# SCH_05_Analog_Mux.net
KiCad netlist of a schematic drawn in Altium Designer
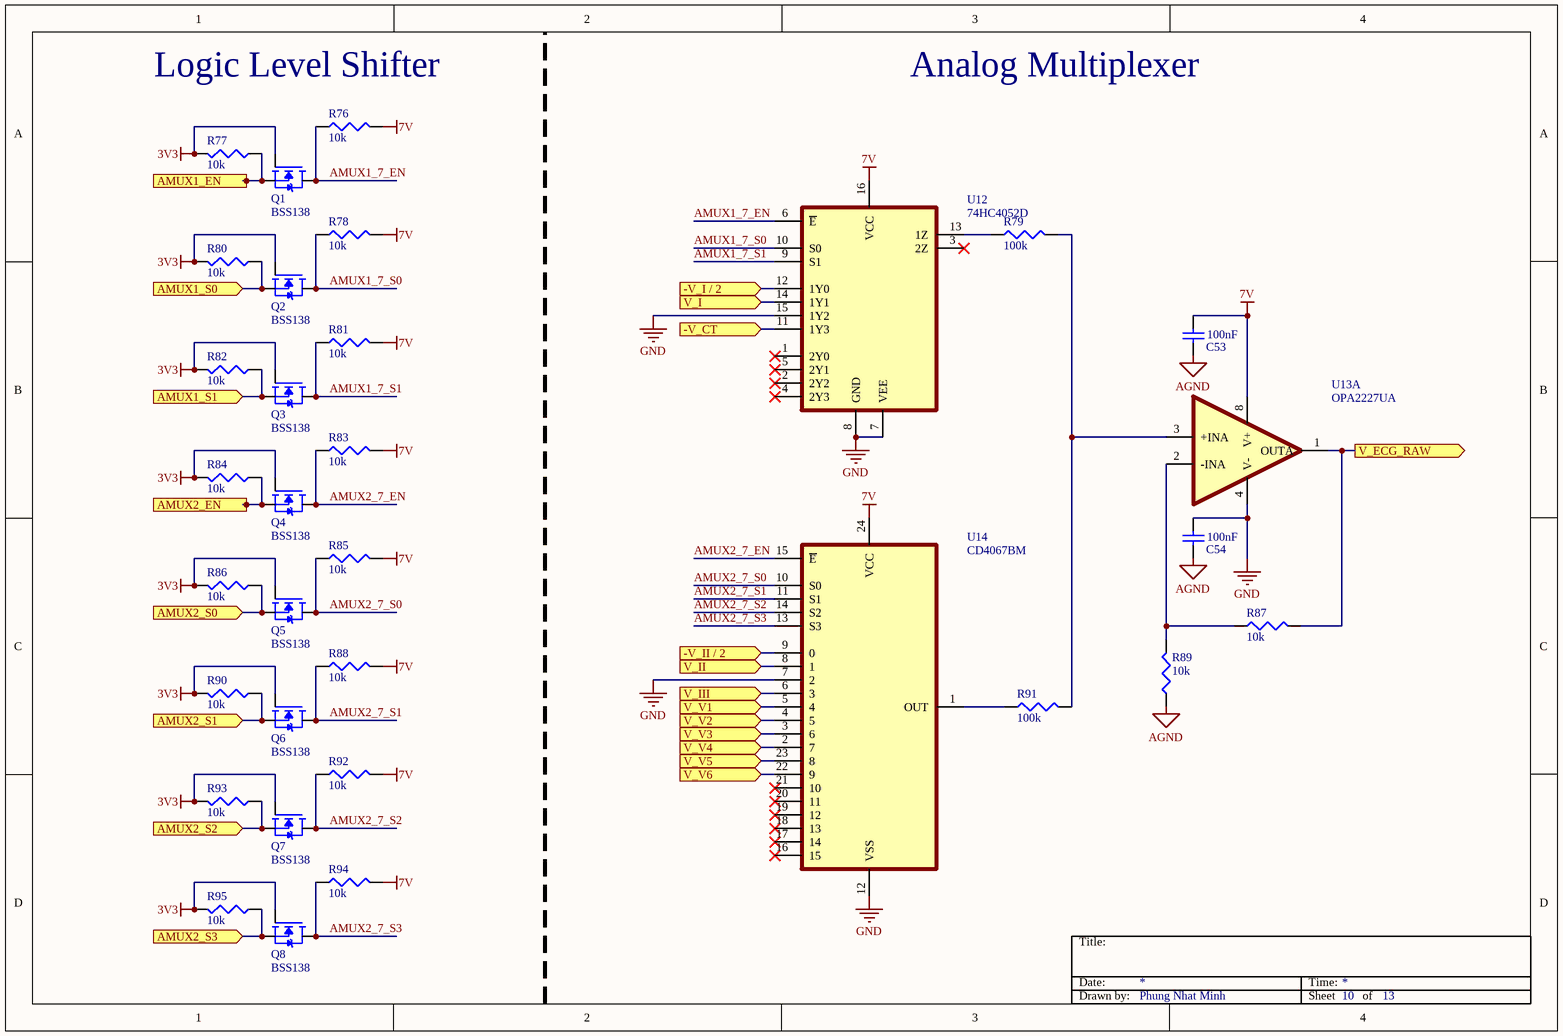
[diagram p0: SCH_05_Analog_Mux.SchDoc]

(export (version "E")
  (design (tool "Eeschema 10.0.6"))
  (components
    (comp (ref "C53")
      (value "100nF")
      (footprint "WCAP-CSGP_0603_L1.6W0.8H0.8_Reflow")
      (description "WCAP-CSGP Multilayer Ceramic Chip Capacitor, General Purpose, size 0603, X7R, 100nF, 50VDC")
      (fields
        (field (name "MANUFACTURER PART NUMBER") "885012206095")
        (field (name "MANUFACTURER") "Wurth Elektronik")
      )
      (libsource (lib "Altium_WCAP-CSGP (rev24b)") (part "885012206095"))
    )
    (comp (ref "C54")
      (value "100nF")
      (footprint "WCAP-CSGP_0603_L1.6W0.8H0.8_Reflow")
      (description "WCAP-CSGP Multilayer Ceramic Chip Capacitor, General Purpose, size 0603, X7R, 100nF, 50VDC")
      (fields
        (field (name "MANUFACTURER PART NUMBER") "885012206095")
        (field (name "MANUFACTURER") "Wurth Elektronik")
      )
      (libsource (lib "Altium_WCAP-CSGP (rev24b)") (part "885012206095"))
    )
    (comp (ref "Q1")
      (value "BSS138")
      (footprint "SOT95P240X111-3N")
      (description "N-Channel 50V 220mA (Ta) 360mW (Ta) Surface Mount SOT-23-3")
      (fields (field (name "MF") "ON Semiconductor"))
      (libsource (lib "BSS138") (part "BSS138"))
    )
    (comp (ref "Q2")
      (value "BSS138")
      (footprint "SOT95P240X111-3N")
      (description "N-Channel 50V 220mA (Ta) 360mW (Ta) Surface Mount SOT-23-3")
      (fields (field (name "MF") "ON Semiconductor"))
      (libsource (lib "BSS138") (part "BSS138"))
    )
    (comp (ref "Q3")
      (value "BSS138")
      (footprint "SOT95P240X111-3N")
      (description "N-Channel 50V 220mA (Ta) 360mW (Ta) Surface Mount SOT-23-3")
      (fields (field (name "MF") "ON Semiconductor"))
      (libsource (lib "BSS138") (part "BSS138"))
    )
    (comp (ref "Q4")
      (value "BSS138")
      (footprint "SOT95P240X111-3N")
      (description "N-Channel 50V 220mA (Ta) 360mW (Ta) Surface Mount SOT-23-3")
      (fields (field (name "MF") "ON Semiconductor"))
      (libsource (lib "BSS138") (part "BSS138"))
    )
    (comp (ref "Q5")
      (value "BSS138")
      (footprint "SOT95P240X111-3N")
      (description "N-Channel 50V 220mA (Ta) 360mW (Ta) Surface Mount SOT-23-3")
      (fields (field (name "MF") "ON Semiconductor"))
      (libsource (lib "BSS138") (part "BSS138"))
    )
    (comp (ref "Q6")
      (value "BSS138")
      (footprint "SOT95P240X111-3N")
      (description "N-Channel 50V 220mA (Ta) 360mW (Ta) Surface Mount SOT-23-3")
      (fields (field (name "MF") "ON Semiconductor"))
      (libsource (lib "BSS138") (part "BSS138"))
    )
    (comp (ref "Q7")
      (value "BSS138")
      (footprint "SOT95P240X111-3N")
      (description "N-Channel 50V 220mA (Ta) 360mW (Ta) Surface Mount SOT-23-3")
      (fields (field (name "MF") "ON Semiconductor"))
      (libsource (lib "BSS138") (part "BSS138"))
    )
    (comp (ref "Q8")
      (value "BSS138")
      (footprint "SOT95P240X111-3N")
      (description "N-Channel 50V 220mA (Ta) 360mW (Ta) Surface Mount SOT-23-3")
      (fields (field (name "MF") "ON Semiconductor"))
      (libsource (lib "BSS138") (part "BSS138"))
    )
    (comp (ref "R76")
      (value "10k")
      (footprint "WRIS-PSMB_0603_L1.6W0.8H0.35")
      (description "WRIS-PSMB Metal Plate Resistor, SMT, size 0603, 0.33W, 5mΩ, +/-1%")
      (fields
        (field (name "MANUFACTURER PART NUMBER") "580060716001")
        (field (name "MANUFACTURER") "Wurth Elektronik")
      )
      (libsource (lib "Altium_WRIS-PSMB (rev22a)") (part "580060716001"))
    )
    (comp (ref "R77")
      (value "10k")
      (footprint "WRIS-PSMB_0603_L1.6W0.8H0.35")
      (description "WRIS-PSMB Metal Plate Resistor, SMT, size 0603, 0.33W, 5mΩ, +/-1%")
      (fields
        (field (name "MANUFACTURER PART NUMBER") "580060716001")
        (field (name "MANUFACTURER") "Wurth Elektronik")
      )
      (libsource (lib "Altium_WRIS-PSMB (rev22a)") (part "580060716001"))
    )
    (comp (ref "R78")
      (value "10k")
      (footprint "WRIS-PSMB_0603_L1.6W0.8H0.35")
      (description "WRIS-PSMB Metal Plate Resistor, SMT, size 0603, 0.33W, 5mΩ, +/-1%")
      (fields
        (field (name "MANUFACTURER PART NUMBER") "580060716001")
        (field (name "MANUFACTURER") "Wurth Elektronik")
      )
      (libsource (lib "Altium_WRIS-PSMB (rev22a)") (part "580060716001"))
    )
    (comp (ref "R79")
      (value "100k")
      (footprint "WRIS-PSMB_0603_L1.6W0.8H0.35")
      (description "WRIS-PSMB Metal Plate Resistor, SMT, size 0603, 0.33W, 5mΩ, +/-1%")
      (fields
        (field (name "MANUFACTURER PART NUMBER") "580060716001")
        (field (name "MANUFACTURER") "Wurth Elektronik")
      )
      (libsource (lib "Altium_WRIS-PSMB (rev22a)") (part "580060716001"))
    )
    (comp (ref "R80")
      (value "10k")
      (footprint "WRIS-PSMB_0603_L1.6W0.8H0.35")
      (description "WRIS-PSMB Metal Plate Resistor, SMT, size 0603, 0.33W, 5mΩ, +/-1%")
      (fields
        (field (name "MANUFACTURER PART NUMBER") "580060716001")
        (field (name "MANUFACTURER") "Wurth Elektronik")
      )
      (libsource (lib "Altium_WRIS-PSMB (rev22a)") (part "580060716001"))
    )
    (comp (ref "R81")
      (value "10k")
      (footprint "WRIS-PSMB_0603_L1.6W0.8H0.35")
      (description "WRIS-PSMB Metal Plate Resistor, SMT, size 0603, 0.33W, 5mΩ, +/-1%")
      (fields
        (field (name "MANUFACTURER PART NUMBER") "580060716001")
        (field (name "MANUFACTURER") "Wurth Elektronik")
      )
      (libsource (lib "Altium_WRIS-PSMB (rev22a)") (part "580060716001"))
    )
    (comp (ref "R82")
      (value "10k")
      (footprint "WRIS-PSMB_0603_L1.6W0.8H0.35")
      (description "WRIS-PSMB Metal Plate Resistor, SMT, size 0603, 0.33W, 5mΩ, +/-1%")
      (fields
        (field (name "MANUFACTURER PART NUMBER") "580060716001")
        (field (name "MANUFACTURER") "Wurth Elektronik")
      )
      (libsource (lib "Altium_WRIS-PSMB (rev22a)") (part "580060716001"))
    )
    (comp (ref "R83")
      (value "10k")
      (footprint "WRIS-PSMB_0603_L1.6W0.8H0.35")
      (description "WRIS-PSMB Metal Plate Resistor, SMT, size 0603, 0.33W, 5mΩ, +/-1%")
      (fields
        (field (name "MANUFACTURER PART NUMBER") "580060716001")
        (field (name "MANUFACTURER") "Wurth Elektronik")
      )
      (libsource (lib "Altium_WRIS-PSMB (rev22a)") (part "580060716001"))
    )
    (comp (ref "R84")
      (value "10k")
      (footprint "WRIS-PSMB_0603_L1.6W0.8H0.35")
      (description "WRIS-PSMB Metal Plate Resistor, SMT, size 0603, 0.33W, 5mΩ, +/-1%")
      (fields
        (field (name "MANUFACTURER PART NUMBER") "580060716001")
        (field (name "MANUFACTURER") "Wurth Elektronik")
      )
      (libsource (lib "Altium_WRIS-PSMB (rev22a)") (part "580060716001"))
    )
    (comp (ref "R85")
      (value "10k")
      (footprint "WRIS-PSMB_0603_L1.6W0.8H0.35")
      (description "WRIS-PSMB Metal Plate Resistor, SMT, size 0603, 0.33W, 5mΩ, +/-1%")
      (fields
        (field (name "MANUFACTURER PART NUMBER") "580060716001")
        (field (name "MANUFACTURER") "Wurth Elektronik")
      )
      (libsource (lib "Altium_WRIS-PSMB (rev22a)") (part "580060716001"))
    )
    (comp (ref "R86")
      (value "10k")
      (footprint "WRIS-PSMB_0603_L1.6W0.8H0.35")
      (description "WRIS-PSMB Metal Plate Resistor, SMT, size 0603, 0.33W, 5mΩ, +/-1%")
      (fields
        (field (name "MANUFACTURER PART NUMBER") "580060716001")
        (field (name "MANUFACTURER") "Wurth Elektronik")
      )
      (libsource (lib "Altium_WRIS-PSMB (rev22a)") (part "580060716001"))
    )
    (comp (ref "R87")
      (value "10k")
      (footprint "WRIS-PSMB_0603_L1.6W0.8H0.35")
      (description "WRIS-PSMB Metal Plate Resistor, SMT, size 0603, 0.33W, 5mΩ, +/-1%")
      (fields
        (field (name "MANUFACTURER PART NUMBER") "580060716001")
        (field (name "MANUFACTURER") "Wurth Elektronik")
      )
      (libsource (lib "Altium_WRIS-PSMB (rev22a)") (part "580060716001"))
    )
    (comp (ref "R88")
      (value "10k")
      (footprint "WRIS-PSMB_0603_L1.6W0.8H0.35")
      (description "WRIS-PSMB Metal Plate Resistor, SMT, size 0603, 0.33W, 5mΩ, +/-1%")
      (fields
        (field (name "MANUFACTURER PART NUMBER") "580060716001")
        (field (name "MANUFACTURER") "Wurth Elektronik")
      )
      (libsource (lib "Altium_WRIS-PSMB (rev22a)") (part "580060716001"))
    )
    (comp (ref "R89")
      (value "10k")
      (footprint "WRIS-PSMB_0603_L1.6W0.8H0.35")
      (description "WRIS-PSMB Metal Plate Resistor, SMT, size 0603, 0.33W, 5mΩ, +/-1%")
      (fields
        (field (name "MANUFACTURER PART NUMBER") "580060716001")
        (field (name "MANUFACTURER") "Wurth Elektronik")
      )
      (libsource (lib "Altium_WRIS-PSMB (rev22a)") (part "580060716001"))
    )
    (comp (ref "R90")
      (value "10k")
      (footprint "WRIS-PSMB_0603_L1.6W0.8H0.35")
      (description "WRIS-PSMB Metal Plate Resistor, SMT, size 0603, 0.33W, 5mΩ, +/-1%")
      (fields
        (field (name "MANUFACTURER PART NUMBER") "580060716001")
        (field (name "MANUFACTURER") "Wurth Elektronik")
      )
      (libsource (lib "Altium_WRIS-PSMB (rev22a)") (part "580060716001"))
    )
    (comp (ref "R91")
      (value "100k")
      (footprint "WRIS-PSMB_0603_L1.6W0.8H0.35")
      (description "WRIS-PSMB Metal Plate Resistor, SMT, size 0603, 0.33W, 5mΩ, +/-1%")
      (fields
        (field (name "MANUFACTURER PART NUMBER") "580060716001")
        (field (name "MANUFACTURER") "Wurth Elektronik")
      )
      (libsource (lib "Altium_WRIS-PSMB (rev22a)") (part "580060716001"))
    )
    (comp (ref "R92")
      (value "10k")
      (footprint "WRIS-PSMB_0603_L1.6W0.8H0.35")
      (description "WRIS-PSMB Metal Plate Resistor, SMT, size 0603, 0.33W, 5mΩ, +/-1%")
      (fields
        (field (name "MANUFACTURER PART NUMBER") "580060716001")
        (field (name "MANUFACTURER") "Wurth Elektronik")
      )
      (libsource (lib "Altium_WRIS-PSMB (rev22a)") (part "580060716001"))
    )
    (comp (ref "R93")
      (value "10k")
      (footprint "WRIS-PSMB_0603_L1.6W0.8H0.35")
      (description "WRIS-PSMB Metal Plate Resistor, SMT, size 0603, 0.33W, 5mΩ, +/-1%")
      (fields
        (field (name "MANUFACTURER PART NUMBER") "580060716001")
        (field (name "MANUFACTURER") "Wurth Elektronik")
      )
      (libsource (lib "Altium_WRIS-PSMB (rev22a)") (part "580060716001"))
    )
    (comp (ref "R94")
      (value "10k")
      (footprint "WRIS-PSMB_0603_L1.6W0.8H0.35")
      (description "WRIS-PSMB Metal Plate Resistor, SMT, size 0603, 0.33W, 5mΩ, +/-1%")
      (fields
        (field (name "MANUFACTURER PART NUMBER") "580060716001")
        (field (name "MANUFACTURER") "Wurth Elektronik")
      )
      (libsource (lib "Altium_WRIS-PSMB (rev22a)") (part "580060716001"))
    )
    (comp (ref "R95")
      (value "10k")
      (footprint "WRIS-PSMB_0603_L1.6W0.8H0.35")
      (description "WRIS-PSMB Metal Plate Resistor, SMT, size 0603, 0.33W, 5mΩ, +/-1%")
      (fields
        (field (name "MANUFACTURER PART NUMBER") "580060716001")
        (field (name "MANUFACTURER") "Wurth Elektronik")
      )
      (libsource (lib "Altium_WRIS-PSMB (rev22a)") (part "580060716001"))
    )
    (comp (ref "U12")
      (value "74HC4052D")
      (footprint "SOIC127P600X175-16N")
      (description "2 Circuit IC Switch 4:1 150Ohm 16-SO")
      (fields (field (name "MP") "74HC4052D,653") (field (name "MF") "Nexperia USA"))
      (libsource (lib "74HC4052D_653") (part "74HC4052D"))
    )
    (comp (ref "U13")
      (value "OPA2227UA")
      (footprint "SOIC127P599X175-8N")
      (libsource (lib "OPA2277UA") (part "OPA2227UA"))
    )
    (comp (ref "U14")
      (value "CD4067BM")
      (footprint "SOIC127P1030X265-24N")
      (libsource (lib "CD4067BM") (part "CD4067BM"))
    )
  )
  (nets
    (net (code "1") (name "/-V_CT") (class "Default")
      (node (ref "U12") (pin "11") (pinfunction "1Y3_11") (pintype "passive"))
    )
    (net (code "2") (name "/-V_I {slash} 2") (class "Default")
      (node (ref "U12") (pin "12") (pinfunction "1Y0_12") (pintype "passive"))
    )
    (net (code "3") (name "/-V_II {slash} 2") (class "Default")
      (node (ref "U14") (pin "9") (pinfunction "0_9") (pintype "passive"))
    )
    (net (code "4") (name "/AMUX1_7_EN") (class "Default")
      (node (ref "Q1") (pin "3") (pinfunction "D_3") (pintype "passive"))
      (node (ref "R76") (pin "1") (pinfunction "1_1") (pintype "passive"))
      (node (ref "U12") (pin "6") (pinfunction "~{E}_6") (pintype "passive"))
    )
    (net (code "5") (name "/AMUX1_7_S0") (class "Default")
      (node (ref "Q2") (pin "3") (pinfunction "D_3") (pintype "passive"))
      (node (ref "R78") (pin "1") (pinfunction "1_1") (pintype "passive"))
      (node (ref "U12") (pin "10") (pinfunction "S0_10") (pintype "passive"))
    )
    (net (code "6") (name "/AMUX1_7_S1") (class "Default")
      (node (ref "Q3") (pin "3") (pinfunction "D_3") (pintype "passive"))
      (node (ref "R81") (pin "1") (pinfunction "1_1") (pintype "passive"))
      (node (ref "U12") (pin "9") (pinfunction "S1_9") (pintype "passive"))
    )
    (net (code "7") (name "/AMUX1_EN") (class "Default")
      (node (ref "Q1") (pin "2") (pinfunction "S_2") (pintype "passive"))
      (node (ref "R77") (pin "1") (pinfunction "1_1") (pintype "passive"))
    )
    (net (code "8") (name "/AMUX1_S0") (class "Default")
      (node (ref "Q2") (pin "2") (pinfunction "S_2") (pintype "passive"))
      (node (ref "R80") (pin "1") (pinfunction "1_1") (pintype "passive"))
    )
    (net (code "9") (name "/AMUX1_S1") (class "Default")
      (node (ref "Q3") (pin "2") (pinfunction "S_2") (pintype "passive"))
      (node (ref "R82") (pin "1") (pinfunction "1_1") (pintype "passive"))
    )
    (net (code "10") (name "/AMUX2_7_EN") (class "Default")
      (node (ref "Q4") (pin "3") (pinfunction "D_3") (pintype "passive"))
      (node (ref "R83") (pin "1") (pinfunction "1_1") (pintype "passive"))
      (node (ref "U14") (pin "15") (pinfunction "~{E}_15") (pintype "passive"))
    )
    (net (code "11") (name "/AMUX2_7_S0") (class "Default")
      (node (ref "Q5") (pin "3") (pinfunction "D_3") (pintype "passive"))
      (node (ref "R85") (pin "1") (pinfunction "1_1") (pintype "passive"))
      (node (ref "U14") (pin "10") (pinfunction "S0_10") (pintype "passive"))
    )
    (net (code "12") (name "/AMUX2_7_S1") (class "Default")
      (node (ref "Q6") (pin "3") (pinfunction "D_3") (pintype "passive"))
      (node (ref "R88") (pin "1") (pinfunction "1_1") (pintype "passive"))
      (node (ref "U14") (pin "11") (pinfunction "S1_11") (pintype "passive"))
    )
    (net (code "13") (name "/AMUX2_7_S2") (class "Default")
      (node (ref "Q7") (pin "3") (pinfunction "D_3") (pintype "passive"))
      (node (ref "R92") (pin "1") (pinfunction "1_1") (pintype "passive"))
      (node (ref "U14") (pin "14") (pinfunction "S2_14") (pintype "passive"))
    )
    (net (code "14") (name "/AMUX2_7_S3") (class "Default")
      (node (ref "Q8") (pin "3") (pinfunction "D_3") (pintype "passive"))
      (node (ref "R94") (pin "1") (pinfunction "1_1") (pintype "passive"))
      (node (ref "U14") (pin "13") (pinfunction "S3_13") (pintype "passive"))
    )
    (net (code "15") (name "/AMUX2_EN") (class "Default")
      (node (ref "Q4") (pin "2") (pinfunction "S_2") (pintype "passive"))
      (node (ref "R84") (pin "1") (pinfunction "1_1") (pintype "passive"))
    )
    (net (code "16") (name "/AMUX2_S0") (class "Default")
      (node (ref "Q5") (pin "2") (pinfunction "S_2") (pintype "passive"))
      (node (ref "R86") (pin "1") (pinfunction "1_1") (pintype "passive"))
    )
    (net (code "17") (name "/AMUX2_S1") (class "Default")
      (node (ref "Q6") (pin "2") (pinfunction "S_2") (pintype "passive"))
      (node (ref "R90") (pin "1") (pinfunction "1_1") (pintype "passive"))
    )
    (net (code "18") (name "/AMUX2_S2") (class "Default")
      (node (ref "Q7") (pin "2") (pinfunction "S_2") (pintype "passive"))
      (node (ref "R93") (pin "1") (pinfunction "1_1") (pintype "passive"))
    )
    (net (code "19") (name "/AMUX2_S3") (class "Default")
      (node (ref "Q8") (pin "2") (pinfunction "S_2") (pintype "passive"))
      (node (ref "R95") (pin "1") (pinfunction "1_1") (pintype "passive"))
    )
    (net (code "20") (name "/V_ECG_RAW") (class "Default")
      (node (ref "R87") (pin "2") (pinfunction "2_2") (pintype "passive"))
      (node (ref "U13") (pin "1") (pinfunction "OUTA_1") (pintype "passive"))
    )
    (net (code "21") (name "/V_I") (class "Default")
      (node (ref "U12") (pin "14") (pinfunction "1Y1_14") (pintype "passive"))
    )
    (net (code "22") (name "/V_II") (class "Default")
      (node (ref "U14") (pin "8") (pinfunction "1_8") (pintype "passive"))
    )
    (net (code "23") (name "/V_III") (class "Default")
      (node (ref "U14") (pin "6") (pinfunction "3_6") (pintype "passive"))
    )
    (net (code "24") (name "/V_V1") (class "Default")
      (node (ref "U14") (pin "5") (pinfunction "4_5") (pintype "passive"))
    )
    (net (code "25") (name "/V_V2") (class "Default")
      (node (ref "U14") (pin "4") (pinfunction "5_4") (pintype "passive"))
    )
    (net (code "26") (name "/V_V3") (class "Default")
      (node (ref "U14") (pin "3") (pinfunction "6_3") (pintype "passive"))
    )
    (net (code "27") (name "/V_V4") (class "Default")
      (node (ref "U14") (pin "2") (pinfunction "7_2") (pintype "passive"))
    )
    (net (code "28") (name "/V_V5") (class "Default")
      (node (ref "U14") (pin "23") (pinfunction "8_23") (pintype "passive"))
    )
    (net (code "29") (name "/V_V6") (class "Default")
      (node (ref "U14") (pin "22") (pinfunction "9_22") (pintype "passive"))
    )
    (net (code "30") (name "3V3") (class "Default")
      (node (ref "Q1") (pin "1") (pinfunction "G_1") (pintype "passive"))
      (node (ref "Q2") (pin "1") (pinfunction "G_1") (pintype "passive"))
      (node (ref "Q3") (pin "1") (pinfunction "G_1") (pintype "passive"))
      (node (ref "Q4") (pin "1") (pinfunction "G_1") (pintype "passive"))
      (node (ref "Q5") (pin "1") (pinfunction "G_1") (pintype "passive"))
      (node (ref "Q6") (pin "1") (pinfunction "G_1") (pintype "passive"))
      (node (ref "Q7") (pin "1") (pinfunction "G_1") (pintype "passive"))
      (node (ref "Q8") (pin "1") (pinfunction "G_1") (pintype "passive"))
      (node (ref "R77") (pin "2") (pinfunction "2_2") (pintype "passive"))
      (node (ref "R80") (pin "2") (pinfunction "2_2") (pintype "passive"))
      (node (ref "R82") (pin "2") (pinfunction "2_2") (pintype "passive"))
      (node (ref "R84") (pin "2") (pinfunction "2_2") (pintype "passive"))
      (node (ref "R86") (pin "2") (pinfunction "2_2") (pintype "passive"))
      (node (ref "R90") (pin "2") (pinfunction "2_2") (pintype "passive"))
      (node (ref "R93") (pin "2") (pinfunction "2_2") (pintype "passive"))
      (node (ref "R95") (pin "2") (pinfunction "2_2") (pintype "passive"))
    )
    (net (code "31") (name "7V") (class "Default")
      (node (ref "C53") (pin "2") (pinfunction "2_2") (pintype "passive"))
      (node (ref "R76") (pin "2") (pinfunction "2_2") (pintype "passive"))
      (node (ref "R78") (pin "2") (pinfunction "2_2") (pintype "passive"))
      (node (ref "R81") (pin "2") (pinfunction "2_2") (pintype "passive"))
      (node (ref "R83") (pin "2") (pinfunction "2_2") (pintype "passive"))
      (node (ref "R85") (pin "2") (pinfunction "2_2") (pintype "passive"))
      (node (ref "R88") (pin "2") (pinfunction "2_2") (pintype "passive"))
      (node (ref "R92") (pin "2") (pinfunction "2_2") (pintype "passive"))
      (node (ref "R94") (pin "2") (pinfunction "2_2") (pintype "passive"))
      (node (ref "U12") (pin "16") (pinfunction "VCC_16") (pintype "power_in"))
      (node (ref "U13") (pin "8") (pinfunction "V+_8") (pintype "power_in"))
      (node (ref "U14") (pin "24") (pinfunction "VCC_24") (pintype "power_in"))
    )
    (net (code "32") (name "AGND") (class "Default")
      (node (ref "C53") (pin "1") (pinfunction "1_1") (pintype "passive"))
      (node (ref "C54") (pin "1") (pinfunction "1_1") (pintype "passive"))
      (node (ref "R89") (pin "1") (pinfunction "1_1") (pintype "passive"))
    )
    (net (code "33") (name "GND") (class "Default")
      (node (ref "C54") (pin "2") (pinfunction "2_2") (pintype "passive"))
      (node (ref "U12") (pin "15") (pinfunction "1Y2_15") (pintype "passive"))
      (node (ref "U12") (pin "7") (pinfunction "VEE_7") (pintype "power_in"))
      (node (ref "U12") (pin "8") (pinfunction "GND_8") (pintype "power_in"))
      (node (ref "U13") (pin "4") (pinfunction "V-_4") (pintype "power_in"))
      (node (ref "U14") (pin "12") (pinfunction "VSS_12") (pintype "power_in"))
      (node (ref "U14") (pin "7") (pinfunction "2_7") (pintype "passive"))
    )
    (net (code "34") (name "Net-(U12-1Z)") (class "Default")
      (node (ref "R79") (pin "1") (pinfunction "1_1") (pintype "passive"))
      (node (ref "U12") (pin "13") (pinfunction "1Z_13") (pintype "passive"))
    )
    (net (code "35") (name "Net-(U13A-+INA)") (class "Default")
      (node (ref "R79") (pin "2") (pinfunction "2_2") (pintype "passive"))
      (node (ref "R91") (pin "2") (pinfunction "2_2") (pintype "passive"))
      (node (ref "U13") (pin "3") (pinfunction "+INA_3") (pintype "passive"))
    )
    (net (code "36") (name "Net-(U13A--INA)") (class "Default")
      (node (ref "R87") (pin "1") (pinfunction "1_1") (pintype "passive"))
      (node (ref "R89") (pin "2") (pinfunction "2_2") (pintype "passive"))
      (node (ref "U13") (pin "2") (pinfunction "-INA_2") (pintype "passive"))
    )
    (net (code "37") (name "Net-(U14-OUT)") (class "Default")
      (node (ref "R91") (pin "1") (pinfunction "1_1") (pintype "passive"))
      (node (ref "U14") (pin "1") (pinfunction "OUT_1") (pintype "passive"))
    )
    (net (code "38") (name "unconnected-(U12-2Y0-Pad1)") (class "Default")
      (node (ref "U12") (pin "1") (pinfunction "2Y0_1") (pintype "passive+no_connect"))
    )
    (net (code "39") (name "unconnected-(U12-2Y1-Pad5)") (class "Default")
      (node (ref "U12") (pin "5") (pinfunction "2Y1_5") (pintype "passive+no_connect"))
    )
    (net (code "40") (name "unconnected-(U12-2Y2-Pad2)") (class "Default")
      (node (ref "U12") (pin "2") (pinfunction "2Y2_2") (pintype "passive+no_connect"))
    )
    (net (code "41") (name "unconnected-(U12-2Y3-Pad4)") (class "Default")
      (node (ref "U12") (pin "4") (pinfunction "2Y3_4") (pintype "passive+no_connect"))
    )
    (net (code "42") (name "unconnected-(U12-2Z-Pad3)") (class "Default")
      (node (ref "U12") (pin "3") (pinfunction "2Z_3") (pintype "passive+no_connect"))
    )
    (net (code "43") (name "unconnected-(U14-10-Pad21)") (class "Default")
      (node (ref "U14") (pin "21") (pinfunction "10_21") (pintype "passive+no_connect"))
    )
    (net (code "44") (name "unconnected-(U14-11-Pad20)") (class "Default")
      (node (ref "U14") (pin "20") (pinfunction "11_20") (pintype "passive+no_connect"))
    )
    (net (code "45") (name "unconnected-(U14-12-Pad19)") (class "Default")
      (node (ref "U14") (pin "19") (pinfunction "12_19") (pintype "passive+no_connect"))
    )
    (net (code "46") (name "unconnected-(U14-13-Pad18)") (class "Default")
      (node (ref "U14") (pin "18") (pinfunction "13_18") (pintype "passive+no_connect"))
    )
    (net (code "47") (name "unconnected-(U14-14-Pad17)") (class "Default")
      (node (ref "U14") (pin "17") (pinfunction "14_17") (pintype "passive+no_connect"))
    )
    (net (code "48") (name "unconnected-(U14-15-Pad16)") (class "Default")
      (node (ref "U14") (pin "16") (pinfunction "15_16") (pintype "passive+no_connect"))
    )
  )
)
